# RP2040_AWG.net
KiCad netlist of a schematic drawn in EasyEDA Pro
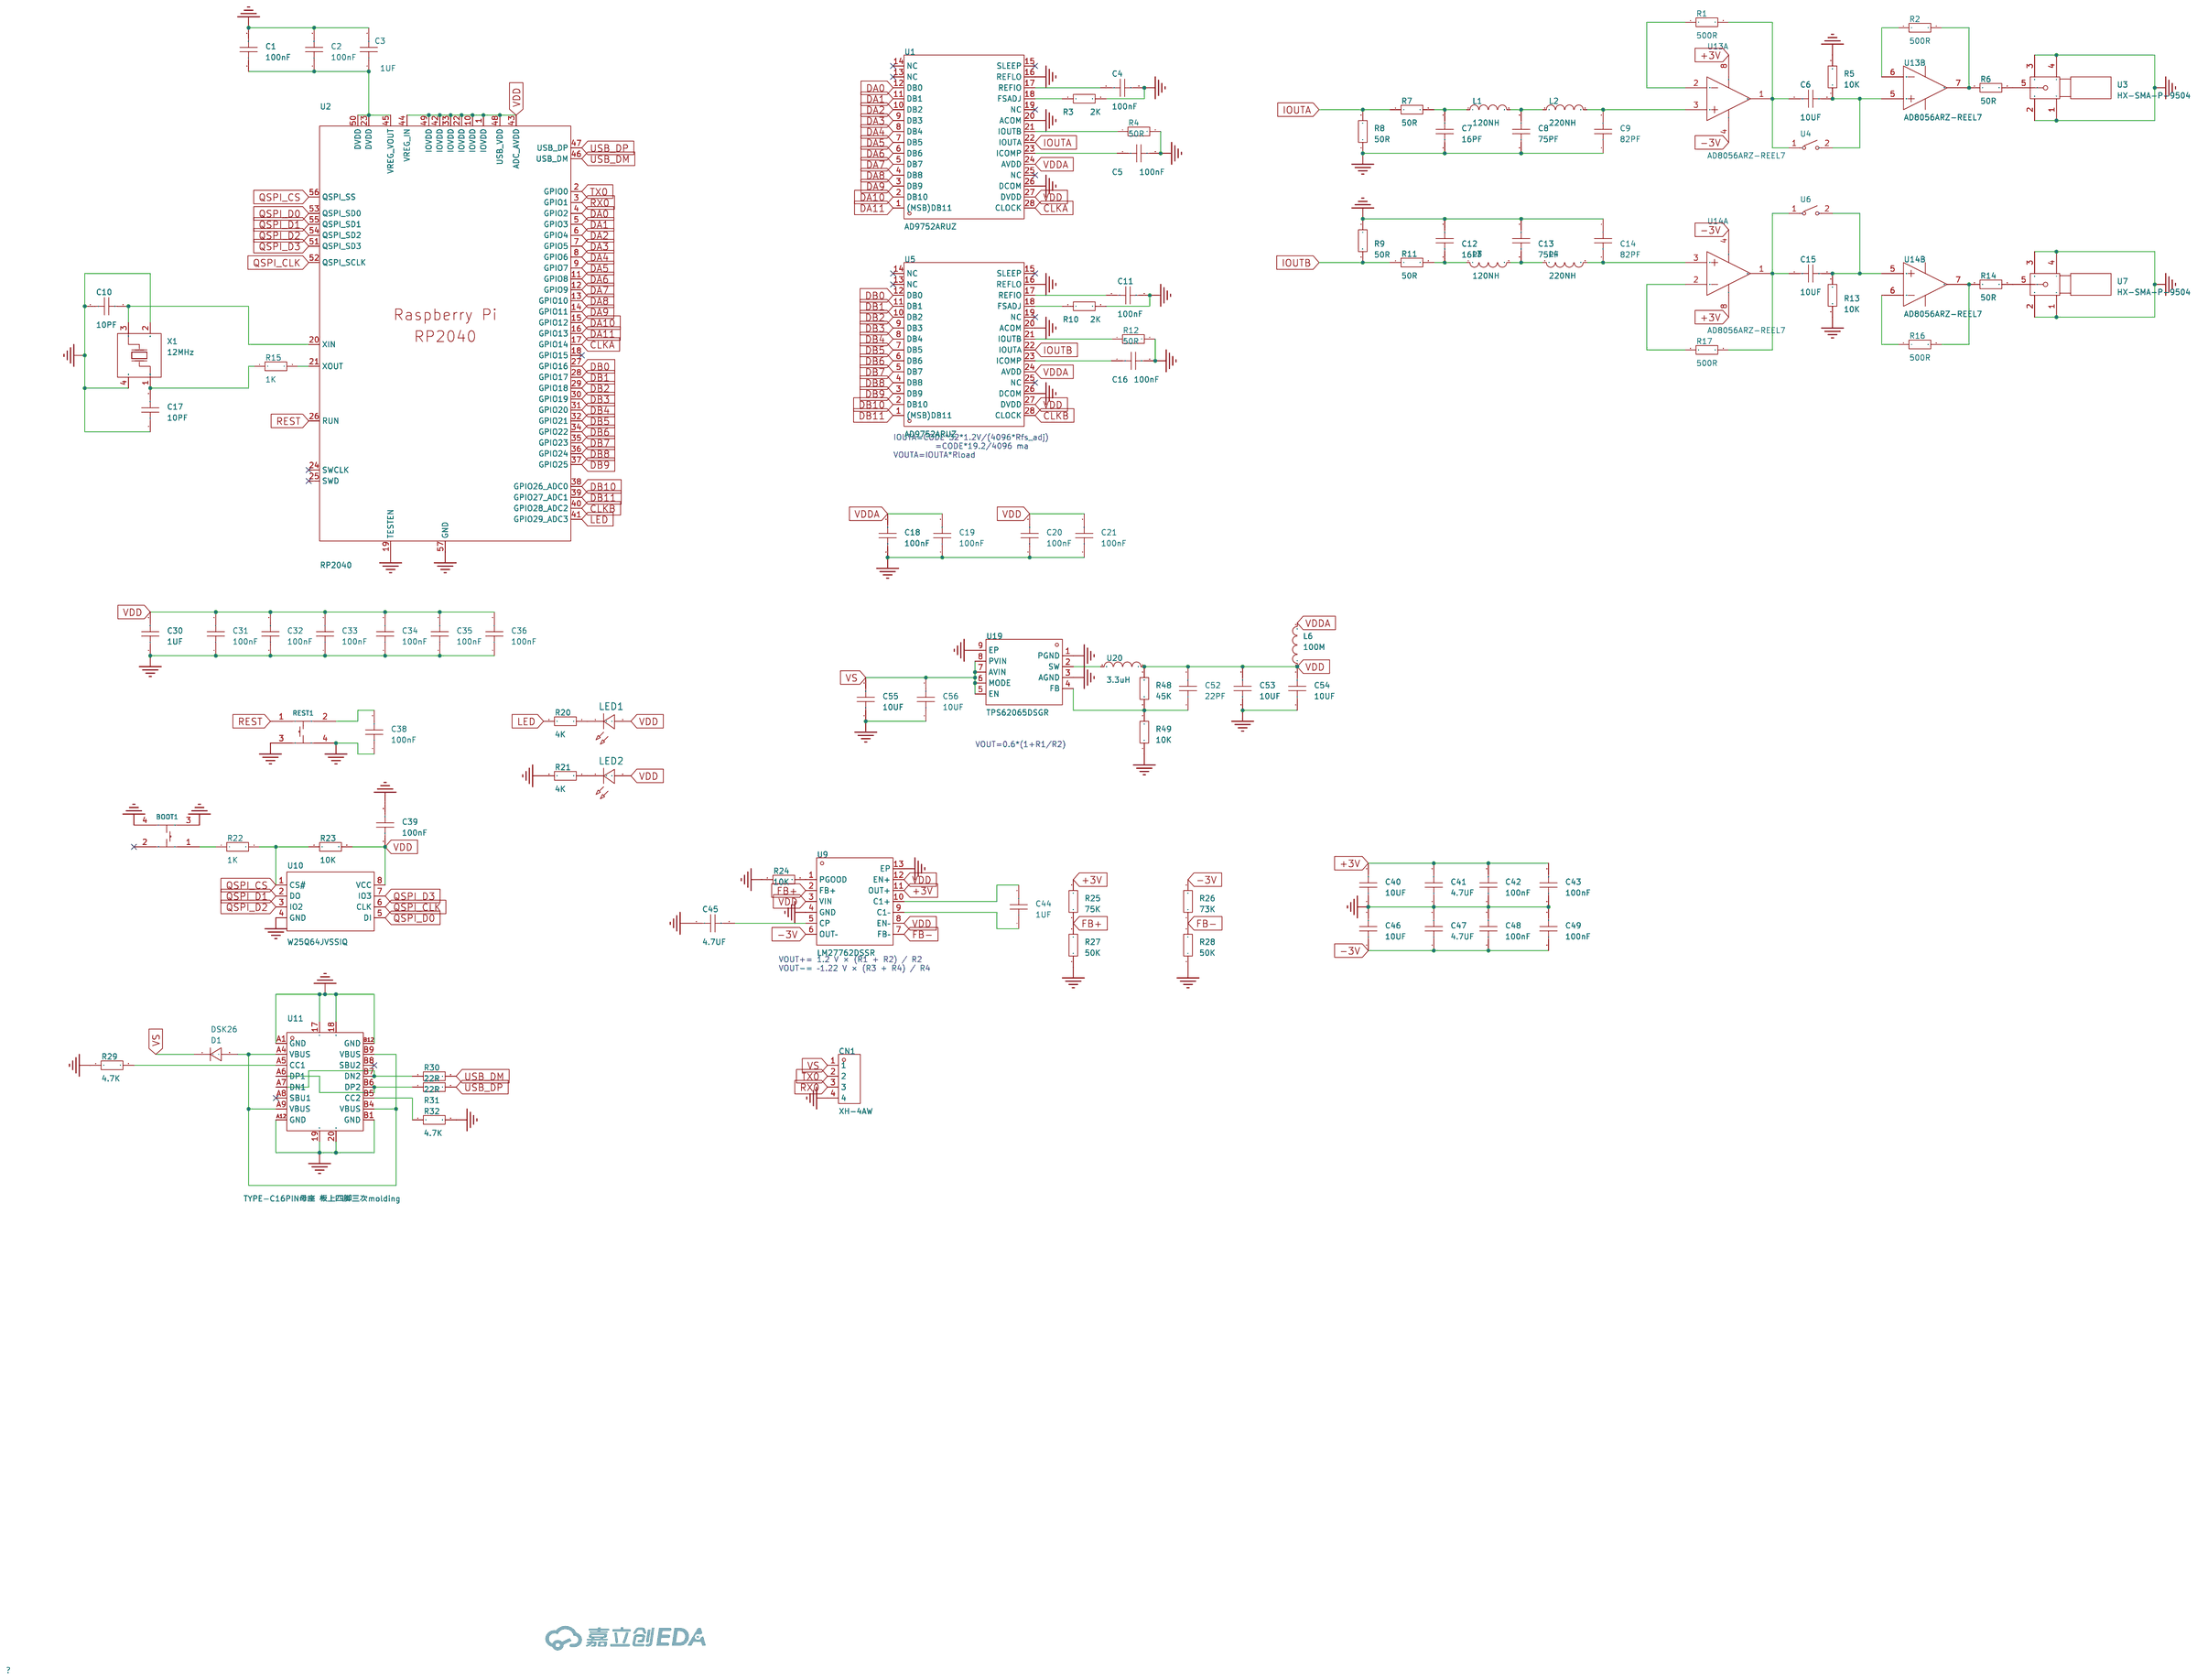
[diagram p0: schematic sheet]

(export (version "E")
  (design (tool "Eeschema 10.0.6"))
  (components
    (comp (ref "BOOT1")
      (value "SKRPACE010")
      (footprint "easyedapro:KEY-SMD_4P-L4.2-W3.2-P2.20-LS4.6")
      (description "电路结构:单刀单掷;按钮形状:椭圆形按钮;安装方式:立贴;开关长度:4.2mm;开关宽度:3.2mm;开关高度:2.5mm;触点电流:50mA;额定电压(DC):16V;带灯:-;机械寿命:-;")
      (fields (field (name "Manufacturer") "ALPSALPINE(阿尔卑斯阿尔派)"))
      (libsource (lib "easyedapro") (part "SKRPACE010"))
    )
    (comp (ref "C1")
      (value "100nF")
      (footprint "easyedapro:C0402_L")
      (libsource (lib "easyedapro") (part "C0402_L"))
    )
    (comp (ref "C2")
      (value "100nF")
      (footprint "easyedapro:C0402_L")
      (libsource (lib "easyedapro") (part "C0402_L"))
    )
    (comp (ref "C3")
      (value "1UF")
      (footprint "easyedapro:C0402_L")
      (libsource (lib "easyedapro") (part "C0402_L"))
    )
    (comp (ref "C4")
      (value "100nF")
      (footprint "easyedapro:C0402_L")
      (libsource (lib "easyedapro") (part "C0402_L"))
    )
    (comp (ref "C5")
      (value "100nF")
      (footprint "easyedapro:C0402_L")
      (libsource (lib "easyedapro") (part "C0402_L"))
    )
    (comp (ref "C6")
      (value "10UF")
      (footprint "easyedapro:C 0603_L")
      (libsource (lib "easyedapro") (part "C0603_L"))
    )
    (comp (ref "C7")
      (value "16PF")
      (footprint "easyedapro:C 0603_L")
      (libsource (lib "easyedapro") (part "C0603_L"))
    )
    (comp (ref "C8")
      (value "75PF")
      (footprint "easyedapro:C 0603_L")
      (libsource (lib "easyedapro") (part "C0603_L"))
    )
    (comp (ref "C9")
      (value "82PF")
      (footprint "easyedapro:C 0603_L")
      (libsource (lib "easyedapro") (part "C0603_L"))
    )
    (comp (ref "C10")
      (value "10PF")
      (footprint "easyedapro:C0402_L")
      (libsource (lib "easyedapro") (part "C0402_L"))
    )
    (comp (ref "C11")
      (value "100nF")
      (footprint "easyedapro:C0402_L")
      (libsource (lib "easyedapro") (part "C0402_L"))
    )
    (comp (ref "C12")
      (value "16PF")
      (footprint "easyedapro:C 0603_L")
      (libsource (lib "easyedapro") (part "C0603_L"))
    )
    (comp (ref "C13")
      (value "75PF")
      (footprint "easyedapro:C 0603_L")
      (libsource (lib "easyedapro") (part "C0603_L"))
    )
    (comp (ref "C14")
      (value "82PF")
      (footprint "easyedapro:C 0603_L")
      (libsource (lib "easyedapro") (part "C0603_L"))
    )
    (comp (ref "C15")
      (value "10UF")
      (footprint "easyedapro:C 0603_L")
      (libsource (lib "easyedapro") (part "C0603_L"))
    )
    (comp (ref "C16")
      (value "100nF")
      (footprint "easyedapro:C0402_L")
      (libsource (lib "easyedapro") (part "C0402_L"))
    )
    (comp (ref "C17")
      (value "10PF")
      (footprint "easyedapro:C0402_L")
      (libsource (lib "easyedapro") (part "C0402_L"))
    )
    (comp (ref "C18")
      (value "100nF")
      (footprint "easyedapro:C0402_L")
      (libsource (lib "easyedapro") (part "C0402_L"))
    )
    (comp (ref "C19")
      (value "100nF")
      (footprint "easyedapro:C0402_L")
      (libsource (lib "easyedapro") (part "C0402_L"))
    )
    (comp (ref "C20")
      (value "100nF")
      (footprint "easyedapro:C0402_L")
      (libsource (lib "easyedapro") (part "C0402_L"))
    )
    (comp (ref "C21")
      (value "100nF")
      (footprint "easyedapro:C0402_L")
      (libsource (lib "easyedapro") (part "C0402_L"))
    )
    (comp (ref "C30")
      (value "1UF")
      (footprint "easyedapro:C0402_L")
      (libsource (lib "easyedapro") (part "C0402_L"))
    )
    (comp (ref "C31")
      (value "100nF")
      (footprint "easyedapro:C0402_L")
      (libsource (lib "easyedapro") (part "C0402_L"))
    )
    (comp (ref "C32")
      (value "100nF")
      (footprint "easyedapro:C0402_L")
      (libsource (lib "easyedapro") (part "C0402_L"))
    )
    (comp (ref "C33")
      (value "100nF")
      (footprint "easyedapro:C0402_L")
      (libsource (lib "easyedapro") (part "C0402_L"))
    )
    (comp (ref "C34")
      (value "100nF")
      (footprint "easyedapro:C0402_L")
      (libsource (lib "easyedapro") (part "C0402_L"))
    )
    (comp (ref "C35")
      (value "100nF")
      (footprint "easyedapro:C0402_L")
      (libsource (lib "easyedapro") (part "C0402_L"))
    )
    (comp (ref "C36")
      (value "100nF")
      (footprint "easyedapro:C0402_L")
      (libsource (lib "easyedapro") (part "C0402_L"))
    )
    (comp (ref "C38")
      (value "100nF")
      (footprint "easyedapro:C0402_L")
      (libsource (lib "easyedapro") (part "C0402_L"))
    )
    (comp (ref "C39")
      (value "100nF")
      (footprint "easyedapro:C0402_L")
      (libsource (lib "easyedapro") (part "C0402_L"))
    )
    (comp (ref "C40")
      (value "10UF")
      (footprint "easyedapro:C0402")
      (libsource (lib "easyedapro") (part "CapAcitance"))
    )
    (comp (ref "C41")
      (value "4.7UF")
      (footprint "easyedapro:C0402")
      (libsource (lib "easyedapro") (part "CapAcitance"))
    )
    (comp (ref "C42")
      (value "100nF")
      (footprint "easyedapro:C0402")
      (libsource (lib "easyedapro") (part "CapAcitance"))
    )
    (comp (ref "C43")
      (value "100nF")
      (footprint "easyedapro:C0402")
      (libsource (lib "easyedapro") (part "CapAcitance"))
    )
    (comp (ref "C44")
      (value "1UF")
      (footprint "easyedapro:C0402")
      (libsource (lib "easyedapro") (part "CapAcitance"))
    )
    (comp (ref "C45")
      (value "4.7UF")
      (footprint "easyedapro:C0402")
      (libsource (lib "easyedapro") (part "CapAcitance"))
    )
    (comp (ref "C46")
      (value "10UF")
      (footprint "easyedapro:C0402")
      (libsource (lib "easyedapro") (part "CapAcitance"))
    )
    (comp (ref "C47")
      (value "4.7UF")
      (footprint "easyedapro:C0402")
      (libsource (lib "easyedapro") (part "CapAcitance"))
    )
    (comp (ref "C48")
      (value "100nF")
      (footprint "easyedapro:C0402")
      (libsource (lib "easyedapro") (part "CapAcitance"))
    )
    (comp (ref "C49")
      (value "100nF")
      (footprint "easyedapro:C0402")
      (libsource (lib "easyedapro") (part "CapAcitance"))
    )
    (comp (ref "C52")
      (value "22PF")
      (footprint "easyedapro:C0402_L")
      (libsource (lib "easyedapro") (part "C0402_L"))
    )
    (comp (ref "C53")
      (value "10UF")
      (footprint "easyedapro:C0402_L")
      (libsource (lib "easyedapro") (part "C0402_L"))
    )
    (comp (ref "C54")
      (value "10UF")
      (footprint "easyedapro:C0402_L")
      (libsource (lib "easyedapro") (part "C0402_L"))
    )
    (comp (ref "C55")
      (value "10UF")
      (footprint "easyedapro:C0402_L")
      (libsource (lib "easyedapro") (part "C0402_L"))
    )
    (comp (ref "C56")
      (value "10UF")
      (footprint "easyedapro:C0402_L")
      (libsource (lib "easyedapro") (part "C0402_L"))
    )
    (comp (ref "CN1")
      (value "XH-4AW")
      (footprint "easyedapro:CONN-TH_XH-4AW")
      (fields (field (name "Manufacturer") "HCTL(华灿天禄)"))
      (libsource (lib "easyedapro") (part "XH-4AW_C2908613"))
    )
    (comp (ref "D1")
      (value "DSK26")
      (footprint "easyedapro:SOD-123_L2.8-W1.8-LS3.7-RD")
      (description "二极管配置:独立式;正向压降(Vf):700mV@2A;直流反向耐压(Vr):60V;整流电流:2A;")
      (fields (field (name "Manufacturer") "MDD(辰达半导体)"))
      (libsource (lib "easyedapro") (part "DSK26"))
    )
    (comp (ref "L1")
      (value "120NH")
      (footprint "easyedapro:L0603")
      (libsource (lib "easyedapro") (part "SDFL1608S100KTF"))
    )
    (comp (ref "L2")
      (value "220NH")
      (footprint "easyedapro:L0603")
      (libsource (lib "easyedapro") (part "SDFL1608S100KTF"))
    )
    (comp (ref "L3")
      (value "120NH")
      (footprint "easyedapro:L0603")
      (libsource (lib "easyedapro") (part "SDFL1608S100KTF"))
    )
    (comp (ref "L4")
      (value "220NH")
      (footprint "easyedapro:L0603")
      (libsource (lib "easyedapro") (part "SDFL1608S100KTF"))
    )
    (comp (ref "L6")
      (value "100M")
      (footprint "easyedapro:L0805")
      (libsource (lib "easyedapro") (part "SDFL2012S100KTF"))
    )
    (comp (ref "LED1")
      (value "~")
      (footprint "easyedapro:LED_0603")
      (libsource (lib "easyedapro") (part "LED_R"))
    )
    (comp (ref "LED2")
      (value "~")
      (footprint "easyedapro:LED_0603")
      (libsource (lib "easyedapro") (part "LED_R"))
    )
    (comp (ref "R1")
      (value "500R")
      (footprint "easyedapro:R0603_L")
      (libsource (lib "easyedapro") (part "R0603_L"))
    )
    (comp (ref "R2")
      (value "500R")
      (footprint "easyedapro:R0603_L")
      (libsource (lib "easyedapro") (part "R0603_L"))
    )
    (comp (ref "R3")
      (value "2K")
      (footprint "easyedapro:R0603_L")
      (libsource (lib "easyedapro") (part "R0603_L"))
    )
    (comp (ref "R4")
      (value "50R")
      (footprint "easyedapro:R0603_L")
      (libsource (lib "easyedapro") (part "R0603_L"))
    )
    (comp (ref "R5")
      (value "10K")
      (footprint "easyedapro:R0603_L")
      (libsource (lib "easyedapro") (part "R0603_L"))
    )
    (comp (ref "R6")
      (value "50R")
      (footprint "easyedapro:R0603_L")
      (libsource (lib "easyedapro") (part "R0603_L"))
    )
    (comp (ref "R7")
      (value "50R")
      (footprint "easyedapro:R0603_L")
      (libsource (lib "easyedapro") (part "R0603_L"))
    )
    (comp (ref "R8")
      (value "50R")
      (footprint "easyedapro:R0603_L")
      (libsource (lib "easyedapro") (part "R0603_L"))
    )
    (comp (ref "R9")
      (value "50R")
      (footprint "easyedapro:R0603_L")
      (libsource (lib "easyedapro") (part "R0603_L"))
    )
    (comp (ref "R10")
      (value "2K")
      (footprint "easyedapro:R0603_L")
      (libsource (lib "easyedapro") (part "R0603_L"))
    )
    (comp (ref "R11")
      (value "50R")
      (footprint "easyedapro:R0603_L")
      (libsource (lib "easyedapro") (part "R0603_L"))
    )
    (comp (ref "R12")
      (value "50R")
      (footprint "easyedapro:R0603_L")
      (libsource (lib "easyedapro") (part "R0603_L"))
    )
    (comp (ref "R13")
      (value "10K")
      (footprint "easyedapro:R0603_L")
      (libsource (lib "easyedapro") (part "R0603_L"))
    )
    (comp (ref "R14")
      (value "50R")
      (footprint "easyedapro:R0603_L")
      (libsource (lib "easyedapro") (part "R0603_L"))
    )
    (comp (ref "R15")
      (value "1K")
      (footprint "easyedapro:R0603_L")
      (libsource (lib "easyedapro") (part "R0603_L"))
    )
    (comp (ref "R16")
      (value "500R")
      (footprint "easyedapro:R0603_L")
      (libsource (lib "easyedapro") (part "R0603_L"))
    )
    (comp (ref "R17")
      (value "500R")
      (footprint "easyedapro:R0603_L")
      (libsource (lib "easyedapro") (part "R0603_L"))
    )
    (comp (ref "R20")
      (value "4K")
      (footprint "easyedapro:R0603_L")
      (libsource (lib "easyedapro") (part "R0603_L"))
    )
    (comp (ref "R21")
      (value "4K")
      (footprint "easyedapro:R0603_L")
      (libsource (lib "easyedapro") (part "R0603_L"))
    )
    (comp (ref "R22")
      (value "1K")
      (footprint "easyedapro:R0603_L")
      (libsource (lib "easyedapro") (part "R0603_L"))
    )
    (comp (ref "R23")
      (value "10K")
      (footprint "easyedapro:R0603_L")
      (libsource (lib "easyedapro") (part "R0603_L"))
    )
    (comp (ref "R24")
      (value "10K")
      (footprint "easyedapro:R0603_L")
      (libsource (lib "easyedapro") (part "R0603_L"))
    )
    (comp (ref "R25")
      (value "75K")
      (footprint "easyedapro:R0603_L")
      (libsource (lib "easyedapro") (part "R0603_L"))
    )
    (comp (ref "R26")
      (value "73K")
      (footprint "easyedapro:R0603_L")
      (libsource (lib "easyedapro") (part "R0603_L"))
    )
    (comp (ref "R27")
      (value "50K")
      (footprint "easyedapro:R0603_L")
      (libsource (lib "easyedapro") (part "R0603_L"))
    )
    (comp (ref "R28")
      (value "50K")
      (footprint "easyedapro:R0603_L")
      (libsource (lib "easyedapro") (part "R0603_L"))
    )
    (comp (ref "R29")
      (value "4.7K")
      (footprint "easyedapro:R0603_L")
      (libsource (lib "easyedapro") (part "R0603_L"))
    )
    (comp (ref "R30")
      (value "22R")
      (footprint "easyedapro:R0603_L")
      (libsource (lib "easyedapro") (part "R0603_L"))
    )
    (comp (ref "R31")
      (value "22R")
      (footprint "easyedapro:R0603_L")
      (libsource (lib "easyedapro") (part "R0603_L"))
    )
    (comp (ref "R32")
      (value "4.7K")
      (footprint "easyedapro:R0603_L")
      (libsource (lib "easyedapro") (part "R0603_L"))
    )
    (comp (ref "R48")
      (value "45K")
      (footprint "easyedapro:R0603_L")
      (libsource (lib "easyedapro") (part "R0603_L"))
    )
    (comp (ref "R49")
      (value "10K")
      (footprint "easyedapro:R0603_L")
      (libsource (lib "easyedapro") (part "R0603_L"))
    )
    (comp (ref "REST1")
      (value "SKRPACE010")
      (footprint "easyedapro:KEY-SMD_4P-L4.2-W3.2-P2.20-LS4.6")
      (description "电路结构:单刀单掷;按钮形状:椭圆形按钮;安装方式:立贴;开关长度:4.2mm;开关宽度:3.2mm;开关高度:2.5mm;触点电流:50mA;额定电压(DC):16V;带灯:-;机械寿命:-;")
      (fields (field (name "Manufacturer") "ALPSALPINE(阿尔卑斯阿尔派)"))
      (libsource (lib "easyedapro") (part "SKRPACE010"))
    )
    (comp (ref "U1")
      (value "AD9752ARUZ")
      (footprint "easyedapro:TSSOP-28_L9.7-W4.4-P0.65-LS6.4-BL")
      (description "分辨率:12位;接口类型:并行;工作电压:2.7V~5.5V;稳定时间:35ns;INL/DNL:0.5LSB；0.25LSB;")
      (fields (field (name "Manufacturer") "ADI(亚德诺)"))
      (libsource (lib "easyedapro") (part "AD9752ARUZ"))
    )
    (comp (ref "U2")
      (value "RP2040")
      (footprint "easyedapro:LQFN-56_L7.0-W7.0-P0.4-EP")
      (description "CPU内核:-;CPU最大主频:133MHz;应用领域:-;")
      (fields (field (name "Manufacturer") "Raspberry Pi(树莓派)"))
      (libsource (lib "easyedapro") (part "RP2040"))
    )
    (comp (ref "U3")
      (value "HX-SMA-P-9504")
      (footprint "easyedapro:RF-SMA-SMD_HX-SMA-P-9631")
      (fields (field (name "Manufacturer") "环协"))
      (libsource (lib "easyedapro") (part "HX-SMA-P-9504"))
    )
    (comp (ref "U4")
      (value "ZX-1.27BM-1PSMD")
      (footprint "easyedapro:SW-SMD_L5.4-W2.8-LS8.2")
      (description "类型:平拨,凹槽式;电路结构:单刀单掷;开关位数:1位;额定电流:25mA;额定电压:24V;使用寿命:1千次;颜色:黑色;")
      (fields (field (name "Manufacturer") "Megastar(兆星)"))
      (libsource (lib "easyedapro") (part "ZX-1.27BM-1PSMD"))
    )
    (comp (ref "U5")
      (value "AD9752ARUZ")
      (footprint "easyedapro:TSSOP-28_L9.7-W4.4-P0.65-LS6.4-BL")
      (description "分辨率:12位;接口类型:并行;工作电压:2.7V~5.5V;稳定时间:35ns;INL/DNL:0.5LSB；0.25LSB;")
      (fields (field (name "Manufacturer") "ADI(亚德诺)"))
      (libsource (lib "easyedapro") (part "AD9752ARUZ"))
    )
    (comp (ref "U6")
      (value "ZX-1.27BM-1PSMD")
      (footprint "easyedapro:SW-SMD_L5.4-W2.8-LS8.2")
      (description "类型:平拨,凹槽式;电路结构:单刀单掷;开关位数:1位;额定电流:25mA;额定电压:24V;使用寿命:1千次;颜色:黑色;")
      (fields (field (name "Manufacturer") "Megastar(兆星)"))
      (libsource (lib "easyedapro") (part "ZX-1.27BM-1PSMD"))
    )
    (comp (ref "U7")
      (value "HX-SMA-P-9504")
      (footprint "easyedapro:RF-SMA-SMD_HX-SMA-P-9631")
      (fields (field (name "Manufacturer") "环协"))
      (libsource (lib "easyedapro") (part "HX-SMA-P-9504"))
    )
    (comp (ref "U9")
      (value "LM27762DSSR")
      (footprint "easyedapro:WSON-12_L3.0-W2.0-P0.50-BL-EP")
      (description "LM27762 带有集成 LDO 的低噪声正负输出电荷泵")
      (fields (field (name "Manufacturer") "TI(德州仪器)"))
      (libsource (lib "easyedapro") (part "LM27762DSSR"))
    )
    (comp (ref "U10")
      (value "W25Q64JVSSIQ")
      (footprint "easyedapro:SOP-8_L5.3-W5.3-P1.27-LS8.0-BL")
      (description "64M-bit/8M-byte FLASH芯片,SPI接口 133MHz(266/532MHz Dual/Quad-SPI) 比W25Q64FVSSIG更高速度")
      (fields (field (name "Manufacturer") "WINBOND(华邦)"))
      (libsource (lib "easyedapro") (part "W25Q64JVSSIQ"))
    )
    (comp (ref "U11")
      (value "TYPE-C16PIN母座 板上四脚三次molding")
      (footprint "easyedapro:USB-SMD_TYPE-C16PIN")
      (libsource (lib "easyedapro") (part "TYPE-C16PIN母座 板上四脚三次MOLDING"))
    )
    (comp (ref "U13")
      (value "AD8056ARZ-REEL7")
      (footprint "easyedapro:SOP-8_L4.9-W3.9-P1.27-LS6.0-BL")
      (description "放大器数:双路;轨到轨:-;增益带宽积(GBP):-;输入失调电压(Vos):5mV;压摆率(SR):1400V/us;输入偏置电流(Ib):400nA;")
      (fields (field (name "Manufacturer") "ADI(亚德诺)"))
      (libsource (lib "easyedapro") (part "AD8056ARZ-REEL7"))
    )
    (comp (ref "U14")
      (value "AD8056ARZ-REEL7")
      (footprint "easyedapro:SOP-8_L4.9-W3.9-P1.27-LS6.0-BL")
      (description "放大器数:双路;轨到轨:-;增益带宽积(GBP):-;输入失调电压(Vos):5mV;压摆率(SR):1400V/us;输入偏置电流(Ib):400nA;")
      (fields (field (name "Manufacturer") "ADI(亚德诺)"))
      (libsource (lib "easyedapro") (part "AD8056ARZ-REEL7"))
    )
    (comp (ref "U19")
      (value "TPS62065DSGR")
      (footprint "easyedapro:WSON-8_L2.0-W2.0-P0.65-BL-EP")
      (description "功能类型:降压型;输出类型:可调;输入电压:2.9V~6V;输出电压:800mV~6V;输出电流(最大值):2A;")
      (fields (field (name "Manufacturer") "TI(德州仪器)"))
      (libsource (lib "easyedapro") (part "TPS62065DSGR"))
    )
    (comp (ref "U20")
      (value "3.3uH")
      (footprint "easyedapro:IND-SMD_L2.5-W2.0")
      (description "电感值:3.3uH;精度:±20%;饱和电流(Isat):2.5A;类型:一体成型电感;")
      (fields (field (name "Manufacturer Part") "SMMS252010-3R3M") (field (name "Manufacturer") "SXN(顺翔诺)"))
      (libsource (lib "easyedapro") (part "SMMS252010-3R3M"))
    )
    (comp (ref "X1")
      (value "12MHz")
      (footprint "easyedapro:CRYSTAL-SMD_4P-L3.2-W2.5-BL")
      (description "晶振类型:贴片晶振;频率:12MHz;常温频差:±10ppm;外接负载电容:20pF;频率稳定度(全温):±20ppm;")
      (fields (field (name "Manufacturer Part") "X322512MSB4SI") (field (name "Manufacturer") "YXC(扬兴晶振)"))
      (libsource (lib "easyedapro") (part "X322512MSB4SI"))
    )
  )
  (nets
    (net (code "1") (name "+3V") (class "Default")
      (node (ref "C40") (pin "2") (pinfunction "2_2") (pintype "input"))
      (node (ref "C41") (pin "2") (pinfunction "2_2") (pintype "input"))
      (node (ref "C42") (pin "2") (pinfunction "2_2") (pintype "input"))
      (node (ref "C43") (pin "2") (pinfunction "2_2") (pintype "input"))
      (node (ref "R25") (pin "2") (pinfunction "2_2") (pintype "input"))
      (node (ref "U13") (pin "8") (pinfunction "+VS_8") (pintype "unspecified"))
      (node (ref "U14") (pin "8") (pinfunction "+VS_8") (pintype "unspecified"))
      (node (ref "U9") (pin "11") (pinfunction "OUT+_11") (pintype "unspecified"))
    )
    (net (code "2") (name "-3V") (class "Default")
      (node (ref "C46") (pin "1") (pinfunction "1_1") (pintype "input"))
      (node (ref "C47") (pin "1") (pinfunction "1_1") (pintype "input"))
      (node (ref "C48") (pin "1") (pinfunction "1_1") (pintype "input"))
      (node (ref "C49") (pin "1") (pinfunction "1_1") (pintype "input"))
      (node (ref "R26") (pin "2") (pinfunction "2_2") (pintype "input"))
      (node (ref "U13") (pin "4") (pinfunction "-VS_4") (pintype "unspecified"))
      (node (ref "U14") (pin "4") (pinfunction "-VS_4") (pintype "unspecified"))
      (node (ref "U9") (pin "6") (pinfunction "OUT–_6") (pintype "unspecified"))
    )
    (net (code "3") (name "CLKA") (class "Default")
      (node (ref "U1") (pin "28") (pinfunction "CLOCK_28") (pintype "unspecified"))
      (node (ref "U2") (pin "17") (pinfunction "GPIO14_17") (pintype "bidirectional"))
    )
    (net (code "4") (name "CLKB") (class "Default")
      (node (ref "U2") (pin "40") (pinfunction "GPIO28_ADC2_40") (pintype "bidirectional"))
      (node (ref "U5") (pin "28") (pinfunction "CLOCK_28") (pintype "unspecified"))
    )
    (net (code "5") (name "DA0") (class "Default")
      (node (ref "U1") (pin "12") (pinfunction "DB0_12") (pintype "unspecified"))
      (node (ref "U2") (pin "4") (pinfunction "GPIO2_4") (pintype "bidirectional"))
    )
    (net (code "6") (name "DA1") (class "Default")
      (node (ref "U1") (pin "11") (pinfunction "DB1_11") (pintype "unspecified"))
      (node (ref "U2") (pin "5") (pinfunction "GPIO3_5") (pintype "bidirectional"))
    )
    (net (code "7") (name "DA2") (class "Default")
      (node (ref "U1") (pin "10") (pinfunction "DB2_10") (pintype "unspecified"))
      (node (ref "U2") (pin "6") (pinfunction "GPIO4_6") (pintype "bidirectional"))
    )
    (net (code "8") (name "DA3") (class "Default")
      (node (ref "U1") (pin "9") (pinfunction "DB3_9") (pintype "unspecified"))
      (node (ref "U2") (pin "7") (pinfunction "GPIO5_7") (pintype "bidirectional"))
    )
    (net (code "9") (name "DA4") (class "Default")
      (node (ref "U1") (pin "8") (pinfunction "DB4_8") (pintype "unspecified"))
      (node (ref "U2") (pin "8") (pinfunction "GPIO6_8") (pintype "bidirectional"))
    )
    (net (code "10") (name "DA5") (class "Default")
      (node (ref "U1") (pin "7") (pinfunction "DB5_7") (pintype "unspecified"))
      (node (ref "U2") (pin "9") (pinfunction "GPIO7_9") (pintype "bidirectional"))
    )
    (net (code "11") (name "DA6") (class "Default")
      (node (ref "U1") (pin "6") (pinfunction "DB6_6") (pintype "unspecified"))
      (node (ref "U2") (pin "11") (pinfunction "GPIO8_11") (pintype "bidirectional"))
    )
    (net (code "12") (name "DA7") (class "Default")
      (node (ref "U1") (pin "5") (pinfunction "DB7_5") (pintype "unspecified"))
      (node (ref "U2") (pin "12") (pinfunction "GPIO9_12") (pintype "bidirectional"))
    )
    (net (code "13") (name "DA8") (class "Default")
      (node (ref "U1") (pin "4") (pinfunction "DB8_4") (pintype "unspecified"))
      (node (ref "U2") (pin "13") (pinfunction "GPIO10_13") (pintype "bidirectional"))
    )
    (net (code "14") (name "DA9") (class "Default")
      (node (ref "U1") (pin "3") (pinfunction "DB9_3") (pintype "unspecified"))
      (node (ref "U2") (pin "14") (pinfunction "GPIO11_14") (pintype "bidirectional"))
    )
    (net (code "15") (name "DA10") (class "Default")
      (node (ref "U1") (pin "2") (pinfunction "DB10_2") (pintype "unspecified"))
      (node (ref "U2") (pin "15") (pinfunction "GPIO12_15") (pintype "bidirectional"))
    )
    (net (code "16") (name "DA11") (class "Default")
      (node (ref "U1") (pin "1") (pinfunction "(MSB)DB11_1") (pintype "unspecified"))
      (node (ref "U2") (pin "16") (pinfunction "GPIO13_16") (pintype "bidirectional"))
    )
    (net (code "17") (name "DB0") (class "Default")
      (node (ref "U2") (pin "27") (pinfunction "GPIO16_27") (pintype "bidirectional"))
      (node (ref "U5") (pin "12") (pinfunction "DB0_12") (pintype "unspecified"))
    )
    (net (code "18") (name "DB1") (class "Default")
      (node (ref "U2") (pin "28") (pinfunction "GPIO17_28") (pintype "bidirectional"))
      (node (ref "U5") (pin "11") (pinfunction "DB1_11") (pintype "unspecified"))
    )
    (net (code "19") (name "DB2") (class "Default")
      (node (ref "U2") (pin "29") (pinfunction "GPIO18_29") (pintype "bidirectional"))
      (node (ref "U5") (pin "10") (pinfunction "DB2_10") (pintype "unspecified"))
    )
    (net (code "20") (name "DB3") (class "Default")
      (node (ref "U2") (pin "30") (pinfunction "GPIO19_30") (pintype "bidirectional"))
      (node (ref "U5") (pin "9") (pinfunction "DB3_9") (pintype "unspecified"))
    )
    (net (code "21") (name "DB4") (class "Default")
      (node (ref "U2") (pin "31") (pinfunction "GPIO20_31") (pintype "bidirectional"))
      (node (ref "U5") (pin "8") (pinfunction "DB4_8") (pintype "unspecified"))
    )
    (net (code "22") (name "DB5") (class "Default")
      (node (ref "U2") (pin "32") (pinfunction "GPIO21_32") (pintype "bidirectional"))
      (node (ref "U5") (pin "7") (pinfunction "DB5_7") (pintype "unspecified"))
    )
    (net (code "23") (name "DB6") (class "Default")
      (node (ref "U2") (pin "34") (pinfunction "GPIO22_34") (pintype "bidirectional"))
      (node (ref "U5") (pin "6") (pinfunction "DB6_6") (pintype "unspecified"))
    )
    (net (code "24") (name "DB7") (class "Default")
      (node (ref "U2") (pin "35") (pinfunction "GPIO23_35") (pintype "bidirectional"))
      (node (ref "U5") (pin "5") (pinfunction "DB7_5") (pintype "unspecified"))
    )
    (net (code "25") (name "DB8") (class "Default")
      (node (ref "U2") (pin "36") (pinfunction "GPIO24_36") (pintype "bidirectional"))
      (node (ref "U5") (pin "4") (pinfunction "DB8_4") (pintype "unspecified"))
    )
    (net (code "26") (name "DB9") (class "Default")
      (node (ref "U2") (pin "37") (pinfunction "GPIO25_37") (pintype "bidirectional"))
      (node (ref "U5") (pin "3") (pinfunction "DB9_3") (pintype "unspecified"))
    )
    (net (code "27") (name "DB10") (class "Default")
      (node (ref "U2") (pin "38") (pinfunction "GPIO26_ADC0_38") (pintype "bidirectional"))
      (node (ref "U5") (pin "2") (pinfunction "DB10_2") (pintype "unspecified"))
    )
    (net (code "28") (name "DB11") (class "Default")
      (node (ref "U2") (pin "39") (pinfunction "GPIO27_ADC1_39") (pintype "bidirectional"))
      (node (ref "U5") (pin "1") (pinfunction "(MSB)DB11_1") (pintype "unspecified"))
    )
    (net (code "29") (name "FB+") (class "Default")
      (node (ref "R25") (pin "1") (pinfunction "1_1") (pintype "input"))
      (node (ref "R27") (pin "2") (pinfunction "2_2") (pintype "input"))
      (node (ref "U9") (pin "2") (pinfunction "FB+_2") (pintype "unspecified"))
    )
    (net (code "30") (name "FB-") (class "Default")
      (node (ref "R26") (pin "1") (pinfunction "1_1") (pintype "input"))
      (node (ref "R28") (pin "2") (pinfunction "2_2") (pintype "input"))
      (node (ref "U9") (pin "7") (pinfunction "FB–_7") (pintype "unspecified"))
    )
    (net (code "31") (name "GND") (class "Default")
      (node (ref "BOOT1") (pin "3") (pinfunction "3_3") (pintype "input"))
      (node (ref "BOOT1") (pin "4") (pinfunction "4_4") (pintype "input"))
      (node (ref "C1") (pin "2") (pinfunction "2_2") (pintype "input"))
      (node (ref "C10") (pin "1") (pinfunction "1_1") (pintype "input"))
      (node (ref "C11") (pin "2") (pinfunction "2_2") (pintype "input"))
      (node (ref "C12") (pin "1") (pinfunction "1_1") (pintype "input"))
      (node (ref "C13") (pin "1") (pinfunction "1_1") (pintype "input"))
      (node (ref "C14") (pin "1") (pinfunction "1_1") (pintype "input"))
      (node (ref "C16") (pin "2") (pinfunction "2_2") (pintype "input"))
      (node (ref "C17") (pin "1") (pinfunction "1_1") (pintype "input"))
      (node (ref "C18") (pin "1") (pinfunction "1_1") (pintype "input"))
      (node (ref "C19") (pin "1") (pinfunction "1_1") (pintype "input"))
      (node (ref "C2") (pin "2") (pinfunction "2_2") (pintype "input"))
      (node (ref "C20") (pin "1") (pinfunction "1_1") (pintype "input"))
      (node (ref "C21") (pin "1") (pinfunction "1_1") (pintype "input"))
      (node (ref "C3") (pin "2") (pinfunction "2_2") (pintype "input"))
      (node (ref "C30") (pin "1") (pinfunction "1_1") (pintype "input"))
      (node (ref "C31") (pin "1") (pinfunction "1_1") (pintype "input"))
      (node (ref "C32") (pin "1") (pinfunction "1_1") (pintype "input"))
      (node (ref "C33") (pin "1") (pinfunction "1_1") (pintype "input"))
      (node (ref "C34") (pin "1") (pinfunction "1_1") (pintype "input"))
      (node (ref "C35") (pin "1") (pinfunction "1_1") (pintype "input"))
      (node (ref "C36") (pin "1") (pinfunction "1_1") (pintype "input"))
      (node (ref "C38") (pin "1") (pinfunction "1_1") (pintype "input"))
      (node (ref "C39") (pin "2") (pinfunction "2_2") (pintype "input"))
      (node (ref "C4") (pin "2") (pinfunction "2_2") (pintype "input"))
      (node (ref "C40") (pin "1") (pinfunction "1_1") (pintype "input"))
      (node (ref "C41") (pin "1") (pinfunction "1_1") (pintype "input"))
      (node (ref "C42") (pin "1") (pinfunction "1_1") (pintype "input"))
      (node (ref "C43") (pin "1") (pinfunction "1_1") (pintype "input"))
      (node (ref "C45") (pin "1") (pinfunction "1_1") (pintype "input"))
      (node (ref "C46") (pin "2") (pinfunction "2_2") (pintype "input"))
      (node (ref "C47") (pin "2") (pinfunction "2_2") (pintype "input"))
      (node (ref "C48") (pin "2") (pinfunction "2_2") (pintype "input"))
      (node (ref "C49") (pin "2") (pinfunction "2_2") (pintype "input"))
      (node (ref "C5") (pin "2") (pinfunction "2_2") (pintype "input"))
      (node (ref "C53") (pin "1") (pinfunction "1_1") (pintype "input"))
      (node (ref "C54") (pin "1") (pinfunction "1_1") (pintype "input"))
      (node (ref "C55") (pin "1") (pinfunction "1_1") (pintype "input"))
      (node (ref "C56") (pin "1") (pinfunction "1_1") (pintype "input"))
      (node (ref "C7") (pin "1") (pinfunction "1_1") (pintype "input"))
      (node (ref "C8") (pin "1") (pinfunction "1_1") (pintype "input"))
      (node (ref "C9") (pin "1") (pinfunction "1_1") (pintype "input"))
      (node (ref "CN1") (pin "4") (pinfunction "4_4") (pintype "unspecified"))
      (node (ref "R10") (pin "2") (pinfunction "2_2") (pintype "input"))
      (node (ref "R12") (pin "2") (pinfunction "2_2") (pintype "input"))
      (node (ref "R13") (pin "2") (pinfunction "2_2") (pintype "input"))
      (node (ref "R21") (pin "2") (pinfunction "2_2") (pintype "input"))
      (node (ref "R24") (pin "1") (pinfunction "1_1") (pintype "input"))
      (node (ref "R27") (pin "1") (pinfunction "1_1") (pintype "input"))
      (node (ref "R28") (pin "1") (pinfunction "1_1") (pintype "input"))
      (node (ref "R29") (pin "1") (pinfunction "1_1") (pintype "input"))
      (node (ref "R3") (pin "2") (pinfunction "2_2") (pintype "input"))
      (node (ref "R32") (pin "2") (pinfunction "2_2") (pintype "input"))
      (node (ref "R4") (pin "2") (pinfunction "2_2") (pintype "input"))
      (node (ref "R49") (pin "1") (pinfunction "1_1") (pintype "input"))
      (node (ref "R5") (pin "2") (pinfunction "2_2") (pintype "input"))
      (node (ref "R8") (pin "1") (pinfunction "1_1") (pintype "input"))
      (node (ref "R9") (pin "1") (pinfunction "1_1") (pintype "input"))
      (node (ref "REST1") (pin "3") (pinfunction "3_3") (pintype "input"))
      (node (ref "REST1") (pin "4") (pinfunction "4_4") (pintype "input"))
      (node (ref "U1") (pin "16") (pinfunction "REFLO_16") (pintype "unspecified"))
      (node (ref "U1") (pin "20") (pinfunction "ACOM_20") (pintype "unspecified"))
      (node (ref "U1") (pin "26") (pinfunction "DCOM_26") (pintype "unspecified"))
      (node (ref "U10") (pin "4") (pinfunction "GND_4") (pintype "unspecified"))
      (node (ref "U11") (pin "17") (pinfunction "17_17") (pintype "input"))
      (node (ref "U11") (pin "18") (pinfunction "18_18") (pintype "input"))
      (node (ref "U11") (pin "19") (pinfunction "19_19") (pintype "input"))
      (node (ref "U11") (pin "20") (pinfunction "20_20") (pintype "input"))
      (node (ref "U11") (pin "A1") (pinfunction "GND_A1") (pintype "input"))
      (node (ref "U11") (pin "A12") (pinfunction "GND_A12") (pintype "input"))
      (node (ref "U11") (pin "B1") (pinfunction "GND_B1") (pintype "input"))
      (node (ref "U11") (pin "B12") (pinfunction "GND_B12") (pintype "input"))
      (node (ref "U19") (pin "1") (pinfunction "PGND_1") (pintype "unspecified"))
      (node (ref "U19") (pin "3") (pinfunction "AGND_3") (pintype "unspecified"))
      (node (ref "U19") (pin "9") (pinfunction "EP_9") (pintype "unspecified"))
      (node (ref "U2") (pin "19") (pinfunction "TESTEN_19") (pintype "unspecified"))
      (node (ref "U2") (pin "57") (pinfunction "GND_57") (pintype "bidirectional"))
      (node (ref "U3") (pin "1") (pinfunction "1_1") (pintype "unspecified"))
      (node (ref "U3") (pin "2") (pinfunction "2_2") (pintype "unspecified"))
      (node (ref "U3") (pin "3") (pinfunction "3_3") (pintype "unspecified"))
      (node (ref "U3") (pin "4") (pinfunction "4_4") (pintype "unspecified"))
      (node (ref "U5") (pin "16") (pinfunction "REFLO_16") (pintype "unspecified"))
      (node (ref "U5") (pin "20") (pinfunction "ACOM_20") (pintype "unspecified"))
      (node (ref "U5") (pin "26") (pinfunction "DCOM_26") (pintype "unspecified"))
      (node (ref "U7") (pin "1") (pinfunction "1_1") (pintype "unspecified"))
      (node (ref "U7") (pin "2") (pinfunction "2_2") (pintype "unspecified"))
      (node (ref "U7") (pin "3") (pinfunction "3_3") (pintype "unspecified"))
      (node (ref "U7") (pin "4") (pinfunction "4_4") (pintype "unspecified"))
      (node (ref "U9") (pin "13") (pinfunction "EP_13") (pintype "unspecified"))
      (node (ref "U9") (pin "4") (pinfunction "GND_4") (pintype "unspecified"))
      (node (ref "X1") (pin "2") (pinfunction "GND_2") (pintype "unspecified"))
      (node (ref "X1") (pin "4") (pinfunction "GND_4") (pintype "unspecified"))
    )
    (net (code "32") (name "IOUTA") (class "Default")
      (node (ref "R7") (pin "1") (pinfunction "1_1") (pintype "input"))
      (node (ref "R8") (pin "2") (pinfunction "2_2") (pintype "input"))
      (node (ref "U1") (pin "22") (pinfunction "IOUTA_22") (pintype "unspecified"))
    )
    (net (code "33") (name "IOUTB") (class "Default")
      (node (ref "R11") (pin "1") (pinfunction "1_1") (pintype "input"))
      (node (ref "R9") (pin "2") (pinfunction "2_2") (pintype "input"))
      (node (ref "U5") (pin "22") (pinfunction "IOUTA_22") (pintype "unspecified"))
    )
    (net (code "34") (name "LED") (class "Default")
      (node (ref "R20") (pin "2") (pinfunction "2_2") (pintype "input"))
      (node (ref "U2") (pin "41") (pinfunction "GPIO29_ADC3_41") (pintype "bidirectional"))
    )
    (net (code "35") (name "Net-(BOOT1-Pad1)") (class "Default")
      (node (ref "BOOT1") (pin "1") (pinfunction "1_1") (pintype "input"))
      (node (ref "R22") (pin "1") (pinfunction "1_1") (pintype "input"))
    )
    (net (code "36") (name "Net-(C7-Pad2)") (class "Default")
      (node (ref "C7") (pin "2") (pinfunction "2_2") (pintype "input"))
      (node (ref "L1") (pin "1") (pinfunction "1_1") (pintype "unspecified"))
      (node (ref "R7") (pin "2") (pinfunction "2_2") (pintype "input"))
    )
    (net (code "37") (name "Net-(C8-Pad2)") (class "Default")
      (node (ref "C8") (pin "2") (pinfunction "2_2") (pintype "input"))
      (node (ref "L1") (pin "2") (pinfunction "2_2") (pintype "unspecified"))
      (node (ref "L2") (pin "1") (pinfunction "1_1") (pintype "unspecified"))
    )
    (net (code "38") (name "Net-(C12-Pad2)") (class "Default")
      (node (ref "C12") (pin "2") (pinfunction "2_2") (pintype "input"))
      (node (ref "L3") (pin "1") (pinfunction "1_1") (pintype "unspecified"))
      (node (ref "R11") (pin "2") (pinfunction "2_2") (pintype "input"))
    )
    (net (code "39") (name "Net-(C13-Pad2)") (class "Default")
      (node (ref "C13") (pin "2") (pinfunction "2_2") (pintype "input"))
      (node (ref "L3") (pin "2") (pinfunction "2_2") (pintype "unspecified"))
      (node (ref "L4") (pin "1") (pinfunction "1_1") (pintype "unspecified"))
    )
    (net (code "40") (name "Net-(C38-Pad2)") (class "Default")
      (node (ref "C38") (pin "2") (pinfunction "2_2") (pintype "input"))
      (node (ref "REST1") (pin "2") (pinfunction "2_2") (pintype "input"))
    )
    (net (code "41") (name "Net-(D1-A)") (class "Default")
      (node (ref "D1") (pin "2") (pinfunction "A_2") (pintype "unspecified"))
      (node (ref "U11") (pin "A4") (pinfunction "VBUS_A4") (pintype "input"))
      (node (ref "U11") (pin "A9") (pinfunction "VBUS_A9") (pintype "input"))
      (node (ref "U11") (pin "B4") (pinfunction "VBUS_B4") (pintype "input"))
      (node (ref "U11") (pin "B9") (pinfunction "VBUS_B9") (pintype "input"))
    )
    (net (code "42") (name "Net-(LED1-C)") (class "Default")
      (node (ref "LED1") (pin "1") (pinfunction "C_1") (pintype "input"))
      (node (ref "R20") (pin "1") (pinfunction "1_1") (pintype "input"))
    )
    (net (code "43") (name "Net-(LED2-C)") (class "Default")
      (node (ref "LED2") (pin "1") (pinfunction "C_1") (pintype "input"))
      (node (ref "R21") (pin "1") (pinfunction "1_1") (pintype "input"))
    )
    (net (code "44") (name "Net-(R6-Pad2)") (class "Default")
      (node (ref "R6") (pin "2") (pinfunction "2_2") (pintype "input"))
      (node (ref "U3") (pin "5") (pinfunction "5_5") (pintype "unspecified"))
    )
    (net (code "45") (name "Net-(R14-Pad2)") (class "Default")
      (node (ref "R14") (pin "2") (pinfunction "2_2") (pintype "input"))
      (node (ref "U7") (pin "5") (pinfunction "5_5") (pintype "unspecified"))
    )
    (net (code "46") (name "Net-(U1-FSADJ)") (class "Default")
      (node (ref "R3") (pin "1") (pinfunction "1_1") (pintype "input"))
      (node (ref "U1") (pin "18") (pinfunction "FSADJ_18") (pintype "unspecified"))
    )
    (net (code "47") (name "Net-(U1-ICOMP)") (class "Default")
      (node (ref "C5") (pin "1") (pinfunction "1_1") (pintype "input"))
      (node (ref "U1") (pin "23") (pinfunction "ICOMP_23") (pintype "unspecified"))
    )
    (net (code "48") (name "Net-(U1-IOUTB)") (class "Default")
      (node (ref "R4") (pin "1") (pinfunction "1_1") (pintype "input"))
      (node (ref "U1") (pin "21") (pinfunction "IOUTB_21") (pintype "unspecified"))
    )
    (net (code "49") (name "Net-(U1-REFIO)") (class "Default")
      (node (ref "C4") (pin "1") (pinfunction "1_1") (pintype "input"))
      (node (ref "U1") (pin "17") (pinfunction "REFIO_17") (pintype "unspecified"))
    )
    (net (code "50") (name "Net-(U2-VREG_VOUT)") (class "Default")
      (node (ref "C1") (pin "1") (pinfunction "1_1") (pintype "input"))
      (node (ref "C2") (pin "1") (pinfunction "1_1") (pintype "input"))
      (node (ref "C3") (pin "1") (pinfunction "1_1") (pintype "input"))
      (node (ref "U2") (pin "23") (pinfunction "DVDD_23") (pintype "bidirectional"))
      (node (ref "U2") (pin "45") (pinfunction "VREG_VOUT_45") (pintype "bidirectional"))
      (node (ref "U2") (pin "50") (pinfunction "DVDD_50") (pintype "bidirectional"))
    )
    (net (code "51") (name "Net-(U2-XIN)") (class "Default")
      (node (ref "C10") (pin "2") (pinfunction "2_2") (pintype "input"))
      (node (ref "U2") (pin "20") (pinfunction "XIN_20") (pintype "input"))
      (node (ref "X1") (pin "3") (pinfunction "OSC2_3") (pintype "unspecified"))
    )
    (net (code "52") (name "Net-(U2-XOUT)") (class "Default")
      (node (ref "R15") (pin "2") (pinfunction "2_2") (pintype "input"))
      (node (ref "U2") (pin "21") (pinfunction "XOUT_21") (pintype "unspecified"))
    )
    (net (code "53") (name "Net-(U5-FSADJ)") (class "Default")
      (node (ref "R10") (pin "1") (pinfunction "1_1") (pintype "input"))
      (node (ref "U5") (pin "18") (pinfunction "FSADJ_18") (pintype "unspecified"))
    )
    (net (code "54") (name "Net-(U5-ICOMP)") (class "Default")
      (node (ref "C16") (pin "1") (pinfunction "1_1") (pintype "input"))
      (node (ref "U5") (pin "23") (pinfunction "ICOMP_23") (pintype "unspecified"))
    )
    (net (code "55") (name "Net-(U5-IOUTB)") (class "Default")
      (node (ref "R12") (pin "1") (pinfunction "1_1") (pintype "input"))
      (node (ref "U5") (pin "21") (pinfunction "IOUTB_21") (pintype "unspecified"))
    )
    (net (code "56") (name "Net-(U5-REFIO)") (class "Default")
      (node (ref "C11") (pin "1") (pinfunction "1_1") (pintype "input"))
      (node (ref "U5") (pin "17") (pinfunction "REFIO_17") (pintype "unspecified"))
    )
    (net (code "57") (name "Net-(U9-C1+)") (class "Default")
      (node (ref "C44") (pin "2") (pinfunction "2_2") (pintype "input"))
      (node (ref "U9") (pin "10") (pinfunction "C1+_10") (pintype "unspecified"))
    )
    (net (code "58") (name "Net-(U9-C1–)") (class "Default")
      (node (ref "C44") (pin "1") (pinfunction "1_1") (pintype "input"))
      (node (ref "U9") (pin "9") (pinfunction "C1–_9") (pintype "unspecified"))
    )
    (net (code "59") (name "Net-(U9-CP)") (class "Default")
      (node (ref "C45") (pin "2") (pinfunction "2_2") (pintype "input"))
      (node (ref "U9") (pin "5") (pinfunction "CP_5") (pintype "unspecified"))
    )
    (net (code "60") (name "Net-(U9-PGOOD)") (class "Default")
      (node (ref "R24") (pin "2") (pinfunction "2_2") (pintype "input"))
      (node (ref "U9") (pin "1") (pinfunction "PGOOD_1") (pintype "unspecified"))
    )
    (net (code "61") (name "Net-(U11-CC1)") (class "Default")
      (node (ref "R29") (pin "2") (pinfunction "2_2") (pintype "input"))
      (node (ref "U11") (pin "A5") (pinfunction "CC1_A5") (pintype "input"))
    )
    (net (code "62") (name "Net-(U11-CC2)") (class "Default")
      (node (ref "R32") (pin "1") (pinfunction "1_1") (pintype "input"))
      (node (ref "U11") (pin "B5") (pinfunction "CC2_B5") (pintype "input"))
    )
    (net (code "63") (name "Net-(U11-DN1)") (class "Default")
      (node (ref "R30") (pin "1") (pinfunction "1_1") (pintype "input"))
      (node (ref "U11") (pin "A7") (pinfunction "DN1_A7") (pintype "input"))
      (node (ref "U11") (pin "B7") (pinfunction "DN2_B7") (pintype "input"))
    )
    (net (code "64") (name "Net-(U11-DP1)") (class "Default")
      (node (ref "R31") (pin "1") (pinfunction "1_1") (pintype "input"))
      (node (ref "U11") (pin "A6") (pinfunction "DP1_A6") (pintype "input"))
      (node (ref "U11") (pin "B6") (pinfunction "DP2_B6") (pintype "input"))
    )
    (net (code "65") (name "Net-(U13A-+IN_1)") (class "Default")
      (node (ref "C9") (pin "2") (pinfunction "2_2") (pintype "input"))
      (node (ref "L2") (pin "2") (pinfunction "2_2") (pintype "unspecified"))
      (node (ref "U13") (pin "3") (pinfunction "+IN_1_3") (pintype "unspecified"))
    )
    (net (code "66") (name "Net-(U13A--IN_1)") (class "Default")
      (node (ref "R1") (pin "1") (pinfunction "1_1") (pintype "input"))
      (node (ref "U13") (pin "2") (pinfunction "-IN_1_2") (pintype "unspecified"))
    )
    (net (code "67") (name "Net-(U13A-OUT_1)") (class "Default")
      (node (ref "C6") (pin "1") (pinfunction "1_1") (pintype "input"))
      (node (ref "R1") (pin "2") (pinfunction "2_2") (pintype "input"))
      (node (ref "U13") (pin "1") (pinfunction "OUT_1_1") (pintype "output"))
      (node (ref "U4") (pin "1") (pinfunction "1_1") (pintype "unspecified"))
    )
    (net (code "68") (name "Net-(U13B-+IN_2)") (class "Default")
      (node (ref "C6") (pin "2") (pinfunction "2_2") (pintype "input"))
      (node (ref "R5") (pin "1") (pinfunction "1_1") (pintype "input"))
      (node (ref "U13") (pin "5") (pinfunction "+IN_2_5") (pintype "unspecified"))
      (node (ref "U4") (pin "2") (pinfunction "2_2") (pintype "unspecified"))
    )
    (net (code "69") (name "Net-(U13B--IN_2)") (class "Default")
      (node (ref "R2") (pin "1") (pinfunction "1_1") (pintype "input"))
      (node (ref "U13") (pin "6") (pinfunction "-IN_2_6") (pintype "unspecified"))
    )
    (net (code "70") (name "Net-(U13B-OUT_2)") (class "Default")
      (node (ref "R2") (pin "2") (pinfunction "2_2") (pintype "input"))
      (node (ref "R6") (pin "1") (pinfunction "1_1") (pintype "input"))
      (node (ref "U13") (pin "7") (pinfunction "OUT_2_7") (pintype "output"))
    )
    (net (code "71") (name "Net-(U14A-+IN_1)") (class "Default")
      (node (ref "C14") (pin "2") (pinfunction "2_2") (pintype "input"))
      (node (ref "L4") (pin "2") (pinfunction "2_2") (pintype "unspecified"))
      (node (ref "U14") (pin "3") (pinfunction "+IN_1_3") (pintype "unspecified"))
    )
    (net (code "72") (name "Net-(U14A--IN_1)") (class "Default")
      (node (ref "R17") (pin "1") (pinfunction "1_1") (pintype "input"))
      (node (ref "U14") (pin "2") (pinfunction "-IN_1_2") (pintype "unspecified"))
    )
    (net (code "73") (name "Net-(U14A-OUT_1)") (class "Default")
      (node (ref "C15") (pin "1") (pinfunction "1_1") (pintype "input"))
      (node (ref "R17") (pin "2") (pinfunction "2_2") (pintype "input"))
      (node (ref "U14") (pin "1") (pinfunction "OUT_1_1") (pintype "output"))
      (node (ref "U6") (pin "1") (pinfunction "1_1") (pintype "unspecified"))
    )
    (net (code "74") (name "Net-(U14B-+IN_2)") (class "Default")
      (node (ref "C15") (pin "2") (pinfunction "2_2") (pintype "input"))
      (node (ref "R13") (pin "1") (pinfunction "1_1") (pintype "input"))
      (node (ref "U14") (pin "5") (pinfunction "+IN_2_5") (pintype "unspecified"))
      (node (ref "U6") (pin "2") (pinfunction "2_2") (pintype "unspecified"))
    )
    (net (code "75") (name "Net-(U14B--IN_2)") (class "Default")
      (node (ref "R16") (pin "1") (pinfunction "1_1") (pintype "input"))
      (node (ref "U14") (pin "6") (pinfunction "-IN_2_6") (pintype "unspecified"))
    )
    (net (code "76") (name "Net-(U14B-OUT_2)") (class "Default")
      (node (ref "R14") (pin "1") (pinfunction "1_1") (pintype "input"))
      (node (ref "R16") (pin "2") (pinfunction "2_2") (pintype "input"))
      (node (ref "U14") (pin "7") (pinfunction "OUT_2_7") (pintype "output"))
    )
    (net (code "77") (name "Net-(U19-FB)") (class "Default")
      (node (ref "C52") (pin "1") (pinfunction "1_1") (pintype "input"))
      (node (ref "R48") (pin "1") (pinfunction "1_1") (pintype "input"))
      (node (ref "R49") (pin "2") (pinfunction "2_2") (pintype "input"))
      (node (ref "U19") (pin "4") (pinfunction "FB_4") (pintype "unspecified"))
    )
    (net (code "78") (name "Net-(U19-SW)") (class "Default")
      (node (ref "U19") (pin "2") (pinfunction "SW_2") (pintype "unspecified"))
      (node (ref "U20") (pin "2") (pinfunction "2_2") (pintype "unspecified"))
    )
    (net (code "79") (name "Net-(X1-OSC1)") (class "Default")
      (node (ref "C17") (pin "2") (pinfunction "2_2") (pintype "input"))
      (node (ref "R15") (pin "1") (pinfunction "1_1") (pintype "input"))
      (node (ref "X1") (pin "1") (pinfunction "OSC1_1") (pintype "unspecified"))
    )
    (net (code "80") (name "QSPI_CLK") (class "Default")
      (node (ref "U10") (pin "6") (pinfunction "CLK_6") (pintype "unspecified"))
      (node (ref "U2") (pin "52") (pinfunction "QSPI_SCLK_52") (pintype "output"))
    )
    (net (code "81") (name "QSPI_CS") (class "Default")
      (node (ref "R22") (pin "2") (pinfunction "2_2") (pintype "input"))
      (node (ref "R23") (pin "1") (pinfunction "1_1") (pintype "input"))
      (node (ref "U10") (pin "1") (pinfunction "CS#_1") (pintype "unspecified"))
      (node (ref "U2") (pin "56") (pinfunction "QSPI_SS_56") (pintype "bidirectional"))
    )
    (net (code "82") (name "QSPI_D0") (class "Default")
      (node (ref "U10") (pin "5") (pinfunction "DI_5") (pintype "unspecified"))
      (node (ref "U2") (pin "53") (pinfunction "QSPI_SD0_53") (pintype "bidirectional"))
    )
    (net (code "83") (name "QSPI_D1") (class "Default")
      (node (ref "U10") (pin "2") (pinfunction "DO_2") (pintype "unspecified"))
      (node (ref "U2") (pin "55") (pinfunction "QSPI_SD1_55") (pintype "bidirectional"))
    )
    (net (code "84") (name "QSPI_D2") (class "Default")
      (node (ref "U10") (pin "3") (pinfunction "IO2_3") (pintype "unspecified"))
      (node (ref "U2") (pin "54") (pinfunction "QSPI_SD2_54") (pintype "bidirectional"))
    )
    (net (code "85") (name "QSPI_D3") (class "Default")
      (node (ref "U10") (pin "7") (pinfunction "IO3_7") (pintype "unspecified"))
      (node (ref "U2") (pin "51") (pinfunction "QSPI_SD3_51") (pintype "bidirectional"))
    )
    (net (code "86") (name "REST") (class "Default")
      (node (ref "REST1") (pin "1") (pinfunction "1_1") (pintype "input"))
      (node (ref "U2") (pin "26") (pinfunction "RUN_26") (pintype "input"))
    )
    (net (code "87") (name "RX0") (class "Default")
      (node (ref "CN1") (pin "3") (pinfunction "3_3") (pintype "unspecified"))
      (node (ref "U2") (pin "3") (pinfunction "GPIO1_3") (pintype "bidirectional"))
    )
    (net (code "88") (name "TX0") (class "Default")
      (node (ref "CN1") (pin "2") (pinfunction "2_2") (pintype "unspecified"))
      (node (ref "U2") (pin "2") (pinfunction "GPIO0_2") (pintype "bidirectional"))
    )
    (net (code "89") (name "USB_DM") (class "Default")
      (node (ref "R30") (pin "2") (pinfunction "2_2") (pintype "input"))
      (node (ref "U2") (pin "46") (pinfunction "USB_DM_46") (pintype "bidirectional"))
    )
    (net (code "90") (name "USB_DP") (class "Default")
      (node (ref "R31") (pin "2") (pinfunction "2_2") (pintype "input"))
      (node (ref "U2") (pin "47") (pinfunction "USB_DP_47") (pintype "bidirectional"))
    )
    (net (code "91") (name "VDD") (class "Default")
      (node (ref "C20") (pin "2") (pinfunction "2_2") (pintype "input"))
      (node (ref "C21") (pin "2") (pinfunction "2_2") (pintype "input"))
      (node (ref "C30") (pin "2") (pinfunction "2_2") (pintype "input"))
      (node (ref "C31") (pin "2") (pinfunction "2_2") (pintype "input"))
      (node (ref "C32") (pin "2") (pinfunction "2_2") (pintype "input"))
      (node (ref "C33") (pin "2") (pinfunction "2_2") (pintype "input"))
      (node (ref "C34") (pin "2") (pinfunction "2_2") (pintype "input"))
      (node (ref "C35") (pin "2") (pinfunction "2_2") (pintype "input"))
      (node (ref "C36") (pin "2") (pinfunction "2_2") (pintype "input"))
      (node (ref "C39") (pin "1") (pinfunction "1_1") (pintype "input"))
      (node (ref "C52") (pin "2") (pinfunction "2_2") (pintype "input"))
      (node (ref "C53") (pin "2") (pinfunction "2_2") (pintype "input"))
      (node (ref "C54") (pin "2") (pinfunction "2_2") (pintype "input"))
      (node (ref "L6") (pin "1") (pinfunction "1_1") (pintype "unspecified"))
      (node (ref "LED1") (pin "2") (pinfunction "A_2") (pintype "input"))
      (node (ref "LED2") (pin "2") (pinfunction "A_2") (pintype "input"))
      (node (ref "R23") (pin "2") (pinfunction "2_2") (pintype "input"))
      (node (ref "R48") (pin "2") (pinfunction "2_2") (pintype "input"))
      (node (ref "U1") (pin "27") (pinfunction "DVDD_27") (pintype "unspecified"))
      (node (ref "U10") (pin "8") (pinfunction "VCC_8") (pintype "unspecified"))
      (node (ref "U2") (pin "1") (pinfunction "IOVDD_1") (pintype "bidirectional"))
      (node (ref "U2") (pin "10") (pinfunction "IOVDD_10") (pintype "bidirectional"))
      (node (ref "U2") (pin "22") (pinfunction "IOVDD_22") (pintype "bidirectional"))
      (node (ref "U2") (pin "33") (pinfunction "IOVDD_33") (pintype "bidirectional"))
      (node (ref "U2") (pin "42") (pinfunction "IOVDD_42") (pintype "bidirectional"))
      (node (ref "U2") (pin "43") (pinfunction "ADC_AVDD_43") (pintype "bidirectional"))
      (node (ref "U2") (pin "44") (pinfunction "VREG_IN_44") (pintype "bidirectional"))
      (node (ref "U2") (pin "48") (pinfunction "USB_VDD_48") (pintype "bidirectional"))
      (node (ref "U2") (pin "49") (pinfunction "IOVDD_49") (pintype "bidirectional"))
      (node (ref "U20") (pin "1") (pinfunction "1_1") (pintype "unspecified"))
      (node (ref "U5") (pin "27") (pinfunction "DVDD_27") (pintype "unspecified"))
      (node (ref "U9") (pin "12") (pinfunction "EN+_12") (pintype "unspecified"))
      (node (ref "U9") (pin "3") (pinfunction "VIN_3") (pintype "unspecified"))
      (node (ref "U9") (pin "8") (pinfunction "EN–_8") (pintype "unspecified"))
    )
    (net (code "92") (name "VDDA") (class "Default")
      (node (ref "C18") (pin "2") (pinfunction "2_2") (pintype "input"))
      (node (ref "C19") (pin "2") (pinfunction "2_2") (pintype "input"))
      (node (ref "L6") (pin "2") (pinfunction "2_2") (pintype "unspecified"))
      (node (ref "U1") (pin "24") (pinfunction "AVDD_24") (pintype "unspecified"))
      (node (ref "U5") (pin "24") (pinfunction "AVDD_24") (pintype "unspecified"))
    )
    (net (code "93") (name "VS") (class "Default")
      (node (ref "C55") (pin "2") (pinfunction "2_2") (pintype "input"))
      (node (ref "C56") (pin "2") (pinfunction "2_2") (pintype "input"))
      (node (ref "CN1") (pin "1") (pinfunction "1_1") (pintype "unspecified"))
      (node (ref "D1") (pin "1") (pinfunction "K_1") (pintype "unspecified"))
      (node (ref "U19") (pin "5") (pinfunction "EN_5") (pintype "unspecified"))
      (node (ref "U19") (pin "6") (pinfunction "MODE_6") (pintype "unspecified"))
      (node (ref "U19") (pin "7") (pinfunction "AVIN_7") (pintype "unspecified"))
      (node (ref "U19") (pin "8") (pinfunction "PVIN_8") (pintype "unspecified"))
    )
    (net (code "94") (name "unconnected-(BOOT1-Pad2)") (class "Default")
      (node (ref "BOOT1") (pin "2") (pinfunction "2_2") (pintype "input+no_connect"))
    )
    (net (code "95") (name "unconnected-(U1-NC-Pad13)") (class "Default")
      (node (ref "U1") (pin "13") (pinfunction "NC_13") (pintype "unspecified+no_connect"))
    )
    (net (code "96") (name "unconnected-(U1-NC-Pad14)") (class "Default")
      (node (ref "U1") (pin "14") (pinfunction "NC_14") (pintype "unspecified+no_connect"))
    )
    (net (code "97") (name "unconnected-(U1-NC-Pad19)") (class "Default")
      (node (ref "U1") (pin "19") (pinfunction "NC_19") (pintype "unspecified+no_connect"))
    )
    (net (code "98") (name "unconnected-(U1-NC-Pad25)") (class "Default")
      (node (ref "U1") (pin "25") (pinfunction "NC_25") (pintype "unspecified+no_connect"))
    )
    (net (code "99") (name "unconnected-(U1-SLEEP-Pad15)") (class "Default")
      (node (ref "U1") (pin "15") (pinfunction "SLEEP_15") (pintype "unspecified+no_connect"))
    )
    (net (code "100") (name "unconnected-(U2-GPIO15-Pad18)") (class "Default")
      (node (ref "U2") (pin "18") (pinfunction "GPIO15_18") (pintype "bidirectional+no_connect"))
    )
    (net (code "101") (name "unconnected-(U2-SWCLK-Pad24)") (class "Default")
      (node (ref "U2") (pin "24") (pinfunction "SWCLK_24") (pintype "output+no_connect"))
    )
    (net (code "102") (name "unconnected-(U2-SWD-Pad25)") (class "Default")
      (node (ref "U2") (pin "25") (pinfunction "SWD_25") (pintype "bidirectional+no_connect"))
    )
    (net (code "103") (name "unconnected-(U5-NC-Pad13)") (class "Default")
      (node (ref "U5") (pin "13") (pinfunction "NC_13") (pintype "unspecified+no_connect"))
    )
    (net (code "104") (name "unconnected-(U5-NC-Pad14)") (class "Default")
      (node (ref "U5") (pin "14") (pinfunction "NC_14") (pintype "unspecified+no_connect"))
    )
    (net (code "105") (name "unconnected-(U5-NC-Pad19)") (class "Default")
      (node (ref "U5") (pin "19") (pinfunction "NC_19") (pintype "unspecified+no_connect"))
    )
    (net (code "106") (name "unconnected-(U5-NC-Pad25)") (class "Default")
      (node (ref "U5") (pin "25") (pinfunction "NC_25") (pintype "unspecified+no_connect"))
    )
    (net (code "107") (name "unconnected-(U5-SLEEP-Pad15)") (class "Default")
      (node (ref "U5") (pin "15") (pinfunction "SLEEP_15") (pintype "unspecified+no_connect"))
    )
    (net (code "108") (name "unconnected-(U11-SBU1-PadA8)") (class "Default")
      (node (ref "U11") (pin "A8") (pinfunction "SBU1_A8") (pintype "input+no_connect"))
    )
    (net (code "109") (name "unconnected-(U11-SBU2-PadB8)") (class "Default")
      (node (ref "U11") (pin "B8") (pinfunction "SBU2_B8") (pintype "input+no_connect"))
    )
  )
)
